# Logic_Probe_Ver_1.net
KiCad netlist of a schematic drawn in EAGLE
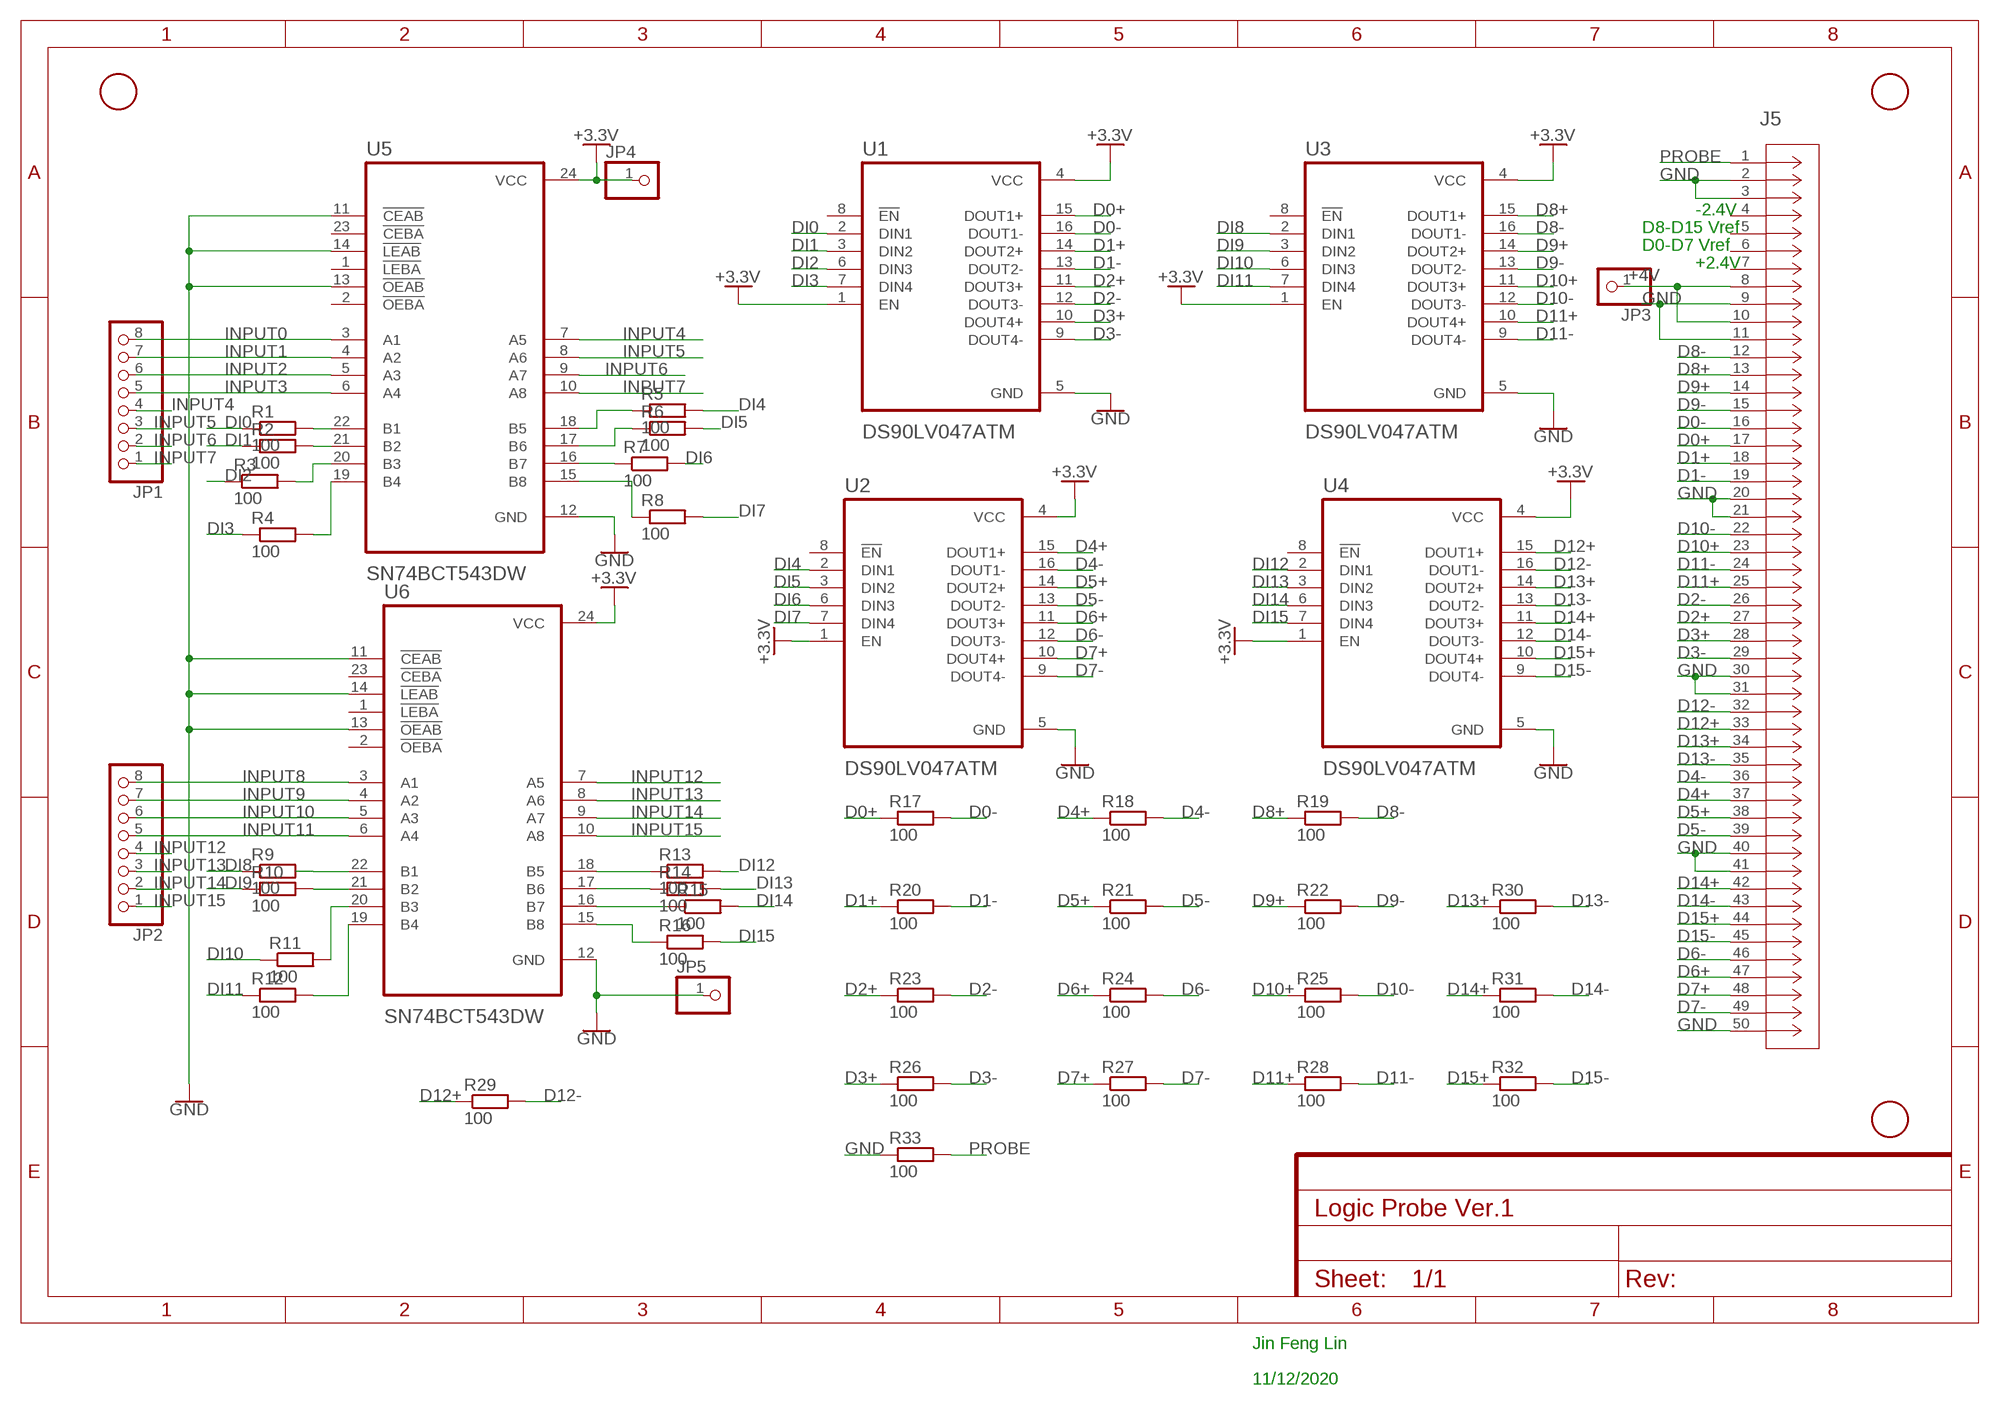
[diagram p0: schematic, sheet 1]

(export (version "E")
  (design (tool "Eeschema 10.0.6"))
  (components
    (comp (ref "J5")
      (value "TST-125-01-G-D")
      (footprint "eagle-import:CONN_TST-125-XX-X-D_SAI")
      (fields (field (name "COPYRIGHT") "Copyright (C) 2018 Accelerated Designs. All rights reserved"))
      (libsource (lib "eagle-import") (part "TST-125-01-G-D"))
    )
    (comp (ref "JP1")
      (value "PINHD-1X8LOCK")
      (footprint "eagle-import:1X08-LOCK")
      (libsource (lib "eagle-import") (part "PINHD-1X8LOCK"))
    )
    (comp (ref "JP2")
      (value "PINHD-1X8LOCK")
      (footprint "eagle-import:1X08-LOCK")
      (libsource (lib "eagle-import") (part "PINHD-1X8LOCK"))
    )
    (comp (ref "JP3")
      (value "PINHD-1X1")
      (footprint "eagle-import:1X01")
      (libsource (lib "eagle-import") (part "PINHD-1X1"))
    )
    (comp (ref "JP4")
      (value "PINHD-1X1")
      (footprint "eagle-import:1X01")
      (libsource (lib "eagle-import") (part "PINHD-1X1"))
    )
    (comp (ref "JP5")
      (value "PINHD-1X1")
      (footprint "eagle-import:1X01")
      (libsource (lib "eagle-import") (part "PINHD-1X1"))
    )
    (comp (ref "R1")
      (value "100")
      (footprint "eagle-import:R0805")
      (libsource (lib "eagle-import") (part "R-EU_R0805"))
    )
    (comp (ref "R2")
      (value "100")
      (footprint "eagle-import:R0805")
      (libsource (lib "eagle-import") (part "R-EU_R0805"))
    )
    (comp (ref "R3")
      (value "100")
      (footprint "eagle-import:R0805")
      (libsource (lib "eagle-import") (part "R-EU_R0805"))
    )
    (comp (ref "R4")
      (value "100")
      (footprint "eagle-import:R0805")
      (libsource (lib "eagle-import") (part "R-EU_R0805"))
    )
    (comp (ref "R5")
      (value "100")
      (footprint "eagle-import:R0805")
      (libsource (lib "eagle-import") (part "R-EU_R0805"))
    )
    (comp (ref "R6")
      (value "100")
      (footprint "eagle-import:R0805")
      (libsource (lib "eagle-import") (part "R-EU_R0805"))
    )
    (comp (ref "R7")
      (value "100")
      (footprint "eagle-import:R0805")
      (libsource (lib "eagle-import") (part "R-EU_R0805"))
    )
    (comp (ref "R8")
      (value "100")
      (footprint "eagle-import:R0805")
      (libsource (lib "eagle-import") (part "R-EU_R0805"))
    )
    (comp (ref "R9")
      (value "100")
      (footprint "eagle-import:R0805")
      (libsource (lib "eagle-import") (part "R-EU_R0805"))
    )
    (comp (ref "R10")
      (value "100")
      (footprint "eagle-import:R0805")
      (libsource (lib "eagle-import") (part "R-EU_R0805"))
    )
    (comp (ref "R11")
      (value "100")
      (footprint "eagle-import:R0805")
      (libsource (lib "eagle-import") (part "R-EU_R0805"))
    )
    (comp (ref "R12")
      (value "100")
      (footprint "eagle-import:R0805")
      (libsource (lib "eagle-import") (part "R-EU_R0805"))
    )
    (comp (ref "R13")
      (value "100")
      (footprint "eagle-import:R0805")
      (libsource (lib "eagle-import") (part "R-EU_R0805"))
    )
    (comp (ref "R14")
      (value "100")
      (footprint "eagle-import:R0805")
      (libsource (lib "eagle-import") (part "R-EU_R0805"))
    )
    (comp (ref "R15")
      (value "100")
      (footprint "eagle-import:R0805")
      (libsource (lib "eagle-import") (part "R-EU_R0805"))
    )
    (comp (ref "R16")
      (value "100")
      (footprint "eagle-import:R0805")
      (libsource (lib "eagle-import") (part "R-EU_R0805"))
    )
    (comp (ref "R17")
      (value "100")
      (footprint "eagle-import:R0805")
      (libsource (lib "eagle-import") (part "R-EU_R0805"))
    )
    (comp (ref "R18")
      (value "100")
      (footprint "eagle-import:R0805")
      (libsource (lib "eagle-import") (part "R-EU_R0805"))
    )
    (comp (ref "R19")
      (value "100")
      (footprint "eagle-import:R0805")
      (libsource (lib "eagle-import") (part "R-EU_R0805"))
    )
    (comp (ref "R20")
      (value "100")
      (footprint "eagle-import:R0805")
      (libsource (lib "eagle-import") (part "R-EU_R0805"))
    )
    (comp (ref "R21")
      (value "100")
      (footprint "eagle-import:R0805")
      (libsource (lib "eagle-import") (part "R-EU_R0805"))
    )
    (comp (ref "R22")
      (value "100")
      (footprint "eagle-import:R0805")
      (libsource (lib "eagle-import") (part "R-EU_R0805"))
    )
    (comp (ref "R23")
      (value "100")
      (footprint "eagle-import:R0805")
      (libsource (lib "eagle-import") (part "R-EU_R0805"))
    )
    (comp (ref "R24")
      (value "100")
      (footprint "eagle-import:R0805")
      (libsource (lib "eagle-import") (part "R-EU_R0805"))
    )
    (comp (ref "R25")
      (value "100")
      (footprint "eagle-import:R0805")
      (libsource (lib "eagle-import") (part "R-EU_R0805"))
    )
    (comp (ref "R26")
      (value "100")
      (footprint "eagle-import:R0805")
      (libsource (lib "eagle-import") (part "R-EU_R0805"))
    )
    (comp (ref "R27")
      (value "100")
      (footprint "eagle-import:R0805")
      (libsource (lib "eagle-import") (part "R-EU_R0805"))
    )
    (comp (ref "R28")
      (value "100")
      (footprint "eagle-import:R0805")
      (libsource (lib "eagle-import") (part "R-EU_R0805"))
    )
    (comp (ref "R29")
      (value "100")
      (footprint "eagle-import:R0805")
      (libsource (lib "eagle-import") (part "R-EU_R0805"))
    )
    (comp (ref "R30")
      (value "100")
      (footprint "eagle-import:R0805")
      (libsource (lib "eagle-import") (part "R-EU_R0805"))
    )
    (comp (ref "R31")
      (value "100")
      (footprint "eagle-import:R0805")
      (libsource (lib "eagle-import") (part "R-EU_R0805"))
    )
    (comp (ref "R32")
      (value "100")
      (footprint "eagle-import:R0805")
      (libsource (lib "eagle-import") (part "R-EU_R0805"))
    )
    (comp (ref "R33")
      (value "100")
      (footprint "eagle-import:R0805")
      (libsource (lib "eagle-import") (part "R-EU_R0805"))
    )
    (comp (ref "U$1")
      (value "FIDUCIAL")
      (footprint "eagle-import:FIDUCIAL_1MM")
      (libsource (lib "eagle-import") (part "FIDUCIAL"))
    )
    (comp (ref "U$2")
      (value "FIDUCIAL")
      (footprint "eagle-import:FIDUCIAL_1MM")
      (libsource (lib "eagle-import") (part "FIDUCIAL"))
    )
    (comp (ref "U$3")
      (value "FIDUCIAL")
      (footprint "eagle-import:FIDUCIAL_1MM")
      (libsource (lib "eagle-import") (part "FIDUCIAL"))
    )
    (comp (ref "U1")
      (value "DS90LV047ATM")
      (footprint "eagle-import:SOIC127P600X175-16N")
      (libsource (lib "eagle-import") (part "DS90LV047ATM"))
    )
    (comp (ref "U2")
      (value "DS90LV047ATM")
      (footprint "eagle-import:SOIC127P600X175-16N")
      (libsource (lib "eagle-import") (part "DS90LV047ATM"))
    )
    (comp (ref "U3")
      (value "DS90LV047ATM")
      (footprint "eagle-import:SOIC127P600X175-16N")
      (libsource (lib "eagle-import") (part "DS90LV047ATM"))
    )
    (comp (ref "U4")
      (value "DS90LV047ATM")
      (footprint "eagle-import:SOIC127P600X175-16N")
      (libsource (lib "eagle-import") (part "DS90LV047ATM"))
    )
    (comp (ref "U5")
      (value "SN74BCT543DW")
      (footprint "eagle-import:SOIC127P1030X265-24N")
      (fields (field (name "MF") "Texas Instruments"))
      (libsource (lib "eagle-import") (part "SN74BCT543DW"))
    )
    (comp (ref "U6")
      (value "SN74BCT543DW")
      (footprint "eagle-import:SOIC127P1030X265-24N")
      (fields (field (name "MF") "Texas Instruments"))
      (libsource (lib "eagle-import") (part "SN74BCT543DW"))
    )
  )
  (nets
    (net (code "1") (name "+3.3V") (class "Default")
      (node (ref "JP4") (pin "1") (pinfunction "1_1") (pintype "passive"))
      (node (ref "U1") (pin "1") (pinfunction "EN_1") (pintype "input"))
      (node (ref "U1") (pin "4") (pinfunction "VCC_4") (pintype "power_in"))
      (node (ref "U2") (pin "1") (pinfunction "EN_1") (pintype "input"))
      (node (ref "U2") (pin "4") (pinfunction "VCC_4") (pintype "power_in"))
      (node (ref "U3") (pin "1") (pinfunction "EN_1") (pintype "input"))
      (node (ref "U3") (pin "4") (pinfunction "VCC_4") (pintype "power_in"))
      (node (ref "U4") (pin "1") (pinfunction "EN_1") (pintype "input"))
      (node (ref "U4") (pin "4") (pinfunction "VCC_4") (pintype "power_in"))
      (node (ref "U5") (pin "24") (pinfunction "VCC_24") (pintype "power_in"))
      (node (ref "U6") (pin "24") (pinfunction "VCC_24") (pintype "power_in"))
    )
    (net (code "2") (name "/+4V") (class "Default")
      (node (ref "J5") (pin "10") (pinfunction "10_10") (pintype "passive"))
      (node (ref "J5") (pin "8") (pinfunction "8_8") (pintype "passive"))
      (node (ref "JP3") (pin "1") (pinfunction "1_1") (pintype "passive"))
    )
    (net (code "3") (name "/D0+") (class "Default")
      (node (ref "J5") (pin "17") (pinfunction "17_17") (pintype "passive"))
      (node (ref "R17") (pin "1") (pinfunction "1_1") (pintype "passive"))
      (node (ref "U1") (pin "15") (pinfunction "DOUT1+_15") (pintype "output"))
    )
    (net (code "4") (name "/D0-") (class "Default")
      (node (ref "J5") (pin "16") (pinfunction "16_16") (pintype "passive"))
      (node (ref "R17") (pin "2") (pinfunction "2_2") (pintype "passive"))
      (node (ref "U1") (pin "16") (pinfunction "DOUT1-_16") (pintype "output"))
    )
    (net (code "5") (name "/D1+") (class "Default")
      (node (ref "J5") (pin "18") (pinfunction "18_18") (pintype "passive"))
      (node (ref "R20") (pin "1") (pinfunction "1_1") (pintype "passive"))
      (node (ref "U1") (pin "14") (pinfunction "DOUT2+_14") (pintype "output"))
    )
    (net (code "6") (name "/D1-") (class "Default")
      (node (ref "J5") (pin "19") (pinfunction "19_19") (pintype "passive"))
      (node (ref "R20") (pin "2") (pinfunction "2_2") (pintype "passive"))
      (node (ref "U1") (pin "13") (pinfunction "DOUT2-_13") (pintype "output"))
    )
    (net (code "7") (name "/D2+") (class "Default")
      (node (ref "J5") (pin "27") (pinfunction "27_27") (pintype "passive"))
      (node (ref "R23") (pin "1") (pinfunction "1_1") (pintype "passive"))
      (node (ref "U1") (pin "11") (pinfunction "DOUT3+_11") (pintype "output"))
    )
    (net (code "8") (name "/D2-") (class "Default")
      (node (ref "J5") (pin "26") (pinfunction "26_26") (pintype "passive"))
      (node (ref "R23") (pin "2") (pinfunction "2_2") (pintype "passive"))
      (node (ref "U1") (pin "12") (pinfunction "DOUT3-_12") (pintype "output"))
    )
    (net (code "9") (name "/D3+") (class "Default")
      (node (ref "J5") (pin "28") (pinfunction "28_28") (pintype "passive"))
      (node (ref "R26") (pin "1") (pinfunction "1_1") (pintype "passive"))
      (node (ref "U1") (pin "10") (pinfunction "DOUT4+_10") (pintype "output"))
    )
    (net (code "10") (name "/D3-") (class "Default")
      (node (ref "J5") (pin "29") (pinfunction "29_29") (pintype "passive"))
      (node (ref "R26") (pin "2") (pinfunction "2_2") (pintype "passive"))
      (node (ref "U1") (pin "9") (pinfunction "DOUT4-_9") (pintype "output"))
    )
    (net (code "11") (name "/D4+") (class "Default")
      (node (ref "J5") (pin "37") (pinfunction "37_37") (pintype "passive"))
      (node (ref "R18") (pin "1") (pinfunction "1_1") (pintype "passive"))
      (node (ref "U2") (pin "15") (pinfunction "DOUT1+_15") (pintype "output"))
    )
    (net (code "12") (name "/D4-") (class "Default")
      (node (ref "J5") (pin "36") (pinfunction "36_36") (pintype "passive"))
      (node (ref "R18") (pin "2") (pinfunction "2_2") (pintype "passive"))
      (node (ref "U2") (pin "16") (pinfunction "DOUT1-_16") (pintype "output"))
    )
    (net (code "13") (name "/D5+") (class "Default")
      (node (ref "J5") (pin "38") (pinfunction "38_38") (pintype "passive"))
      (node (ref "R21") (pin "1") (pinfunction "1_1") (pintype "passive"))
      (node (ref "U2") (pin "14") (pinfunction "DOUT2+_14") (pintype "output"))
    )
    (net (code "14") (name "/D5-") (class "Default")
      (node (ref "J5") (pin "39") (pinfunction "39_39") (pintype "passive"))
      (node (ref "R21") (pin "2") (pinfunction "2_2") (pintype "passive"))
      (node (ref "U2") (pin "13") (pinfunction "DOUT2-_13") (pintype "output"))
    )
    (net (code "15") (name "/D6+") (class "Default")
      (node (ref "J5") (pin "47") (pinfunction "47_47") (pintype "passive"))
      (node (ref "R24") (pin "1") (pinfunction "1_1") (pintype "passive"))
      (node (ref "U2") (pin "11") (pinfunction "DOUT3+_11") (pintype "output"))
    )
    (net (code "16") (name "/D6-") (class "Default")
      (node (ref "J5") (pin "46") (pinfunction "46_46") (pintype "passive"))
      (node (ref "R24") (pin "2") (pinfunction "2_2") (pintype "passive"))
      (node (ref "U2") (pin "12") (pinfunction "DOUT3-_12") (pintype "output"))
    )
    (net (code "17") (name "/D7+") (class "Default")
      (node (ref "J5") (pin "48") (pinfunction "48_48") (pintype "passive"))
      (node (ref "R27") (pin "1") (pinfunction "1_1") (pintype "passive"))
      (node (ref "U2") (pin "10") (pinfunction "DOUT4+_10") (pintype "output"))
    )
    (net (code "18") (name "/D7-") (class "Default")
      (node (ref "J5") (pin "49") (pinfunction "49_49") (pintype "passive"))
      (node (ref "R27") (pin "2") (pinfunction "2_2") (pintype "passive"))
      (node (ref "U2") (pin "9") (pinfunction "DOUT4-_9") (pintype "output"))
    )
    (net (code "19") (name "/D8+") (class "Default")
      (node (ref "J5") (pin "13") (pinfunction "13_13") (pintype "passive"))
      (node (ref "R19") (pin "1") (pinfunction "1_1") (pintype "passive"))
      (node (ref "U3") (pin "15") (pinfunction "DOUT1+_15") (pintype "output"))
    )
    (net (code "20") (name "/D8-") (class "Default")
      (node (ref "J5") (pin "12") (pinfunction "12_12") (pintype "passive"))
      (node (ref "R19") (pin "2") (pinfunction "2_2") (pintype "passive"))
      (node (ref "U3") (pin "16") (pinfunction "DOUT1-_16") (pintype "output"))
    )
    (net (code "21") (name "/D9+") (class "Default")
      (node (ref "J5") (pin "14") (pinfunction "14_14") (pintype "passive"))
      (node (ref "R22") (pin "1") (pinfunction "1_1") (pintype "passive"))
      (node (ref "U3") (pin "14") (pinfunction "DOUT2+_14") (pintype "output"))
    )
    (net (code "22") (name "/D9-") (class "Default")
      (node (ref "J5") (pin "15") (pinfunction "15_15") (pintype "passive"))
      (node (ref "R22") (pin "2") (pinfunction "2_2") (pintype "passive"))
      (node (ref "U3") (pin "13") (pinfunction "DOUT2-_13") (pintype "output"))
    )
    (net (code "23") (name "/D10+") (class "Default")
      (node (ref "J5") (pin "23") (pinfunction "23_23") (pintype "passive"))
      (node (ref "R25") (pin "1") (pinfunction "1_1") (pintype "passive"))
      (node (ref "U3") (pin "11") (pinfunction "DOUT3+_11") (pintype "output"))
    )
    (net (code "24") (name "/D10-") (class "Default")
      (node (ref "J5") (pin "22") (pinfunction "22_22") (pintype "passive"))
      (node (ref "R25") (pin "2") (pinfunction "2_2") (pintype "passive"))
      (node (ref "U3") (pin "12") (pinfunction "DOUT3-_12") (pintype "output"))
    )
    (net (code "25") (name "/D11+") (class "Default")
      (node (ref "J5") (pin "25") (pinfunction "25_25") (pintype "passive"))
      (node (ref "R28") (pin "1") (pinfunction "1_1") (pintype "passive"))
      (node (ref "U3") (pin "10") (pinfunction "DOUT4+_10") (pintype "output"))
    )
    (net (code "26") (name "/D11-") (class "Default")
      (node (ref "J5") (pin "24") (pinfunction "24_24") (pintype "passive"))
      (node (ref "R28") (pin "2") (pinfunction "2_2") (pintype "passive"))
      (node (ref "U3") (pin "9") (pinfunction "DOUT4-_9") (pintype "output"))
    )
    (net (code "27") (name "/D12+") (class "Default")
      (node (ref "J5") (pin "33") (pinfunction "33_33") (pintype "passive"))
      (node (ref "R29") (pin "1") (pinfunction "1_1") (pintype "passive"))
      (node (ref "U4") (pin "15") (pinfunction "DOUT1+_15") (pintype "output"))
    )
    (net (code "28") (name "/D12-") (class "Default")
      (node (ref "J5") (pin "32") (pinfunction "32_32") (pintype "passive"))
      (node (ref "R29") (pin "2") (pinfunction "2_2") (pintype "passive"))
      (node (ref "U4") (pin "16") (pinfunction "DOUT1-_16") (pintype "output"))
    )
    (net (code "29") (name "/D13+") (class "Default")
      (node (ref "J5") (pin "34") (pinfunction "34_34") (pintype "passive"))
      (node (ref "R30") (pin "1") (pinfunction "1_1") (pintype "passive"))
      (node (ref "U4") (pin "14") (pinfunction "DOUT2+_14") (pintype "output"))
    )
    (net (code "30") (name "/D13-") (class "Default")
      (node (ref "J5") (pin "35") (pinfunction "35_35") (pintype "passive"))
      (node (ref "R30") (pin "2") (pinfunction "2_2") (pintype "passive"))
      (node (ref "U4") (pin "13") (pinfunction "DOUT2-_13") (pintype "output"))
    )
    (net (code "31") (name "/D14+") (class "Default")
      (node (ref "J5") (pin "42") (pinfunction "42_42") (pintype "passive"))
      (node (ref "R31") (pin "1") (pinfunction "1_1") (pintype "passive"))
      (node (ref "U4") (pin "11") (pinfunction "DOUT3+_11") (pintype "output"))
    )
    (net (code "32") (name "/D14-") (class "Default")
      (node (ref "J5") (pin "43") (pinfunction "43_43") (pintype "passive"))
      (node (ref "R31") (pin "2") (pinfunction "2_2") (pintype "passive"))
      (node (ref "U4") (pin "12") (pinfunction "DOUT3-_12") (pintype "output"))
    )
    (net (code "33") (name "/D15+") (class "Default")
      (node (ref "J5") (pin "44") (pinfunction "44_44") (pintype "passive"))
      (node (ref "R32") (pin "1") (pinfunction "1_1") (pintype "passive"))
      (node (ref "U4") (pin "10") (pinfunction "DOUT4+_10") (pintype "output"))
    )
    (net (code "34") (name "/D15-") (class "Default")
      (node (ref "J5") (pin "45") (pinfunction "45_45") (pintype "passive"))
      (node (ref "R32") (pin "2") (pinfunction "2_2") (pintype "passive"))
      (node (ref "U4") (pin "9") (pinfunction "DOUT4-_9") (pintype "output"))
    )
    (net (code "35") (name "/DI0") (class "Default")
      (node (ref "R1") (pin "1") (pinfunction "1_1") (pintype "passive"))
      (node (ref "U1") (pin "2") (pinfunction "DIN1_2") (pintype "input"))
    )
    (net (code "36") (name "/DI1") (class "Default")
      (node (ref "R2") (pin "1") (pinfunction "1_1") (pintype "passive"))
      (node (ref "U1") (pin "3") (pinfunction "DIN2_3") (pintype "input"))
    )
    (net (code "37") (name "/DI2") (class "Default")
      (node (ref "R3") (pin "1") (pinfunction "1_1") (pintype "passive"))
      (node (ref "U1") (pin "6") (pinfunction "DIN3_6") (pintype "input"))
    )
    (net (code "38") (name "/DI3") (class "Default")
      (node (ref "R4") (pin "1") (pinfunction "1_1") (pintype "passive"))
      (node (ref "U1") (pin "7") (pinfunction "DIN4_7") (pintype "input"))
    )
    (net (code "39") (name "/DI4") (class "Default")
      (node (ref "R5") (pin "2") (pinfunction "2_2") (pintype "passive"))
      (node (ref "U2") (pin "2") (pinfunction "DIN1_2") (pintype "input"))
    )
    (net (code "40") (name "/DI5") (class "Default")
      (node (ref "R6") (pin "2") (pinfunction "2_2") (pintype "passive"))
      (node (ref "U2") (pin "3") (pinfunction "DIN2_3") (pintype "input"))
    )
    (net (code "41") (name "/DI6") (class "Default")
      (node (ref "R7") (pin "2") (pinfunction "2_2") (pintype "passive"))
      (node (ref "U2") (pin "6") (pinfunction "DIN3_6") (pintype "input"))
    )
    (net (code "42") (name "/DI7") (class "Default")
      (node (ref "R8") (pin "2") (pinfunction "2_2") (pintype "passive"))
      (node (ref "U2") (pin "7") (pinfunction "DIN4_7") (pintype "input"))
    )
    (net (code "43") (name "/DI8") (class "Default")
      (node (ref "R9") (pin "1") (pinfunction "1_1") (pintype "passive"))
      (node (ref "U3") (pin "2") (pinfunction "DIN1_2") (pintype "input"))
    )
    (net (code "44") (name "/DI9") (class "Default")
      (node (ref "R10") (pin "1") (pinfunction "1_1") (pintype "passive"))
      (node (ref "U3") (pin "3") (pinfunction "DIN2_3") (pintype "input"))
    )
    (net (code "45") (name "/DI10") (class "Default")
      (node (ref "R11") (pin "1") (pinfunction "1_1") (pintype "passive"))
      (node (ref "U3") (pin "6") (pinfunction "DIN3_6") (pintype "input"))
    )
    (net (code "46") (name "/DI11") (class "Default")
      (node (ref "R12") (pin "1") (pinfunction "1_1") (pintype "passive"))
      (node (ref "U3") (pin "7") (pinfunction "DIN4_7") (pintype "input"))
    )
    (net (code "47") (name "/DI12") (class "Default")
      (node (ref "R13") (pin "2") (pinfunction "2_2") (pintype "passive"))
      (node (ref "U4") (pin "2") (pinfunction "DIN1_2") (pintype "input"))
    )
    (net (code "48") (name "/DI13") (class "Default")
      (node (ref "R14") (pin "2") (pinfunction "2_2") (pintype "passive"))
      (node (ref "U4") (pin "3") (pinfunction "DIN2_3") (pintype "input"))
    )
    (net (code "49") (name "/DI14") (class "Default")
      (node (ref "R15") (pin "2") (pinfunction "2_2") (pintype "passive"))
      (node (ref "U4") (pin "6") (pinfunction "DIN3_6") (pintype "input"))
    )
    (net (code "50") (name "/DI15") (class "Default")
      (node (ref "R16") (pin "2") (pinfunction "2_2") (pintype "passive"))
      (node (ref "U4") (pin "7") (pinfunction "DIN4_7") (pintype "input"))
    )
    (net (code "51") (name "/INPUT0") (class "Default")
      (node (ref "JP1") (pin "8") (pinfunction "8_8") (pintype "passive"))
      (node (ref "U5") (pin "3") (pinfunction "A1_3") (pintype "bidirectional"))
    )
    (net (code "52") (name "/INPUT1") (class "Default")
      (node (ref "JP1") (pin "7") (pinfunction "7_7") (pintype "passive"))
      (node (ref "U5") (pin "4") (pinfunction "A2_4") (pintype "bidirectional"))
    )
    (net (code "53") (name "/INPUT2") (class "Default")
      (node (ref "JP1") (pin "6") (pinfunction "6_6") (pintype "passive"))
      (node (ref "U5") (pin "5") (pinfunction "A3_5") (pintype "bidirectional"))
    )
    (net (code "54") (name "/INPUT3") (class "Default")
      (node (ref "JP1") (pin "5") (pinfunction "5_5") (pintype "passive"))
      (node (ref "U5") (pin "6") (pinfunction "A4_6") (pintype "bidirectional"))
    )
    (net (code "55") (name "/INPUT4") (class "Default")
      (node (ref "JP1") (pin "4") (pinfunction "4_4") (pintype "passive"))
      (node (ref "U5") (pin "7") (pinfunction "A5_7") (pintype "bidirectional"))
    )
    (net (code "56") (name "/INPUT5") (class "Default")
      (node (ref "JP1") (pin "3") (pinfunction "3_3") (pintype "passive"))
      (node (ref "U5") (pin "8") (pinfunction "A6_8") (pintype "bidirectional"))
    )
    (net (code "57") (name "/INPUT6") (class "Default")
      (node (ref "JP1") (pin "2") (pinfunction "2_2") (pintype "passive"))
      (node (ref "U5") (pin "9") (pinfunction "A7_9") (pintype "bidirectional"))
    )
    (net (code "58") (name "/INPUT7") (class "Default")
      (node (ref "JP1") (pin "1") (pinfunction "1_1") (pintype "passive"))
      (node (ref "U5") (pin "10") (pinfunction "A8_10") (pintype "bidirectional"))
    )
    (net (code "59") (name "/INPUT8") (class "Default")
      (node (ref "JP2") (pin "8") (pinfunction "8_8") (pintype "passive"))
      (node (ref "U6") (pin "3") (pinfunction "A1_3") (pintype "bidirectional"))
    )
    (net (code "60") (name "/INPUT9") (class "Default")
      (node (ref "JP2") (pin "7") (pinfunction "7_7") (pintype "passive"))
      (node (ref "U6") (pin "4") (pinfunction "A2_4") (pintype "bidirectional"))
    )
    (net (code "61") (name "/INPUT10") (class "Default")
      (node (ref "JP2") (pin "6") (pinfunction "6_6") (pintype "passive"))
      (node (ref "U6") (pin "5") (pinfunction "A3_5") (pintype "bidirectional"))
    )
    (net (code "62") (name "/INPUT11") (class "Default")
      (node (ref "JP2") (pin "5") (pinfunction "5_5") (pintype "passive"))
      (node (ref "U6") (pin "6") (pinfunction "A4_6") (pintype "bidirectional"))
    )
    (net (code "63") (name "/INPUT12") (class "Default")
      (node (ref "JP2") (pin "4") (pinfunction "4_4") (pintype "passive"))
      (node (ref "U6") (pin "7") (pinfunction "A5_7") (pintype "bidirectional"))
    )
    (net (code "64") (name "/INPUT13") (class "Default")
      (node (ref "JP2") (pin "3") (pinfunction "3_3") (pintype "passive"))
      (node (ref "U6") (pin "8") (pinfunction "A6_8") (pintype "bidirectional"))
    )
    (net (code "65") (name "/INPUT14") (class "Default")
      (node (ref "JP2") (pin "2") (pinfunction "2_2") (pintype "passive"))
      (node (ref "U6") (pin "9") (pinfunction "A7_9") (pintype "bidirectional"))
    )
    (net (code "66") (name "/INPUT15") (class "Default")
      (node (ref "JP2") (pin "1") (pinfunction "1_1") (pintype "passive"))
      (node (ref "U6") (pin "10") (pinfunction "A8_10") (pintype "bidirectional"))
    )
    (net (code "67") (name "/PROBE") (class "Default")
      (node (ref "J5") (pin "1") (pinfunction "1_1") (pintype "passive"))
      (node (ref "R33") (pin "2") (pinfunction "2_2") (pintype "passive"))
    )
    (net (code "68") (name "GND") (class "Default")
      (node (ref "J5") (pin "11") (pinfunction "11_11") (pintype "passive"))
      (node (ref "J5") (pin "2") (pinfunction "2_2") (pintype "passive"))
      (node (ref "J5") (pin "20") (pinfunction "20_20") (pintype "passive"))
      (node (ref "J5") (pin "21") (pinfunction "21_21") (pintype "passive"))
      (node (ref "J5") (pin "3") (pinfunction "3_3") (pintype "passive"))
      (node (ref "J5") (pin "30") (pinfunction "30_30") (pintype "passive"))
      (node (ref "J5") (pin "31") (pinfunction "31_31") (pintype "passive"))
      (node (ref "J5") (pin "40") (pinfunction "40_40") (pintype "passive"))
      (node (ref "J5") (pin "41") (pinfunction "41_41") (pintype "passive"))
      (node (ref "J5") (pin "50") (pinfunction "50_50") (pintype "passive"))
      (node (ref "J5") (pin "9") (pinfunction "9_9") (pintype "passive"))
      (node (ref "JP5") (pin "1") (pinfunction "1_1") (pintype "passive"))
      (node (ref "R33") (pin "1") (pinfunction "1_1") (pintype "passive"))
      (node (ref "U1") (pin "5") (pinfunction "GND_5") (pintype "power_in"))
      (node (ref "U2") (pin "5") (pinfunction "GND_5") (pintype "power_in"))
      (node (ref "U3") (pin "5") (pinfunction "GND_5") (pintype "power_in"))
      (node (ref "U4") (pin "5") (pinfunction "GND_5") (pintype "power_in"))
      (node (ref "U5") (pin "11") (pinfunction "~{CEAB}_11") (pintype "input"))
      (node (ref "U5") (pin "12") (pinfunction "GND_12") (pintype "power_in"))
      (node (ref "U5") (pin "13") (pinfunction "~{OEAB}_13") (pintype "input"))
      (node (ref "U5") (pin "14") (pinfunction "~{LEAB}_14") (pintype "input"))
      (node (ref "U6") (pin "11") (pinfunction "~{CEAB}_11") (pintype "input"))
      (node (ref "U6") (pin "12") (pinfunction "GND_12") (pintype "power_in"))
      (node (ref "U6") (pin "13") (pinfunction "~{OEAB}_13") (pintype "input"))
      (node (ref "U6") (pin "14") (pinfunction "~{LEAB}_14") (pintype "input"))
    )
    (net (code "69") (name "Net-(U5-B1)") (class "Default")
      (node (ref "R1") (pin "2") (pinfunction "2_2") (pintype "passive"))
      (node (ref "U5") (pin "22") (pinfunction "B1_22") (pintype "bidirectional"))
    )
    (net (code "70") (name "Net-(U5-B2)") (class "Default")
      (node (ref "R2") (pin "2") (pinfunction "2_2") (pintype "passive"))
      (node (ref "U5") (pin "21") (pinfunction "B2_21") (pintype "bidirectional"))
    )
    (net (code "71") (name "Net-(U5-B3)") (class "Default")
      (node (ref "R3") (pin "2") (pinfunction "2_2") (pintype "passive"))
      (node (ref "U5") (pin "20") (pinfunction "B3_20") (pintype "bidirectional"))
    )
    (net (code "72") (name "Net-(U5-B4)") (class "Default")
      (node (ref "R4") (pin "2") (pinfunction "2_2") (pintype "passive"))
      (node (ref "U5") (pin "19") (pinfunction "B4_19") (pintype "bidirectional"))
    )
    (net (code "73") (name "Net-(U5-B5)") (class "Default")
      (node (ref "R5") (pin "1") (pinfunction "1_1") (pintype "passive"))
      (node (ref "U5") (pin "18") (pinfunction "B5_18") (pintype "bidirectional"))
    )
    (net (code "74") (name "Net-(U5-B6)") (class "Default")
      (node (ref "R6") (pin "1") (pinfunction "1_1") (pintype "passive"))
      (node (ref "U5") (pin "17") (pinfunction "B6_17") (pintype "bidirectional"))
    )
    (net (code "75") (name "Net-(U5-B7)") (class "Default")
      (node (ref "R7") (pin "1") (pinfunction "1_1") (pintype "passive"))
      (node (ref "U5") (pin "16") (pinfunction "B7_16") (pintype "bidirectional"))
    )
    (net (code "76") (name "Net-(U5-B8)") (class "Default")
      (node (ref "R8") (pin "1") (pinfunction "1_1") (pintype "passive"))
      (node (ref "U5") (pin "15") (pinfunction "B8_15") (pintype "bidirectional"))
    )
    (net (code "77") (name "Net-(U6-B1)") (class "Default")
      (node (ref "R9") (pin "2") (pinfunction "2_2") (pintype "passive"))
      (node (ref "U6") (pin "22") (pinfunction "B1_22") (pintype "bidirectional"))
    )
    (net (code "78") (name "Net-(U6-B2)") (class "Default")
      (node (ref "R10") (pin "2") (pinfunction "2_2") (pintype "passive"))
      (node (ref "U6") (pin "21") (pinfunction "B2_21") (pintype "bidirectional"))
    )
    (net (code "79") (name "Net-(U6-B3)") (class "Default")
      (node (ref "R11") (pin "2") (pinfunction "2_2") (pintype "passive"))
      (node (ref "U6") (pin "20") (pinfunction "B3_20") (pintype "bidirectional"))
    )
    (net (code "80") (name "Net-(U6-B4)") (class "Default")
      (node (ref "R12") (pin "2") (pinfunction "2_2") (pintype "passive"))
      (node (ref "U6") (pin "19") (pinfunction "B4_19") (pintype "bidirectional"))
    )
    (net (code "81") (name "Net-(U6-B5)") (class "Default")
      (node (ref "R13") (pin "1") (pinfunction "1_1") (pintype "passive"))
      (node (ref "U6") (pin "18") (pinfunction "B5_18") (pintype "bidirectional"))
    )
    (net (code "82") (name "Net-(U6-B6)") (class "Default")
      (node (ref "R14") (pin "1") (pinfunction "1_1") (pintype "passive"))
      (node (ref "U6") (pin "17") (pinfunction "B6_17") (pintype "bidirectional"))
    )
    (net (code "83") (name "Net-(U6-B7)") (class "Default")
      (node (ref "R15") (pin "1") (pinfunction "1_1") (pintype "passive"))
      (node (ref "U6") (pin "16") (pinfunction "B7_16") (pintype "bidirectional"))
    )
    (net (code "84") (name "Net-(U6-B8)") (class "Default")
      (node (ref "R16") (pin "1") (pinfunction "1_1") (pintype "passive"))
      (node (ref "U6") (pin "15") (pinfunction "B8_15") (pintype "bidirectional"))
    )
    (net (code "85") (name "unconnected-(J5-Pad4)") (class "Default")
      (node (ref "J5") (pin "4") (pinfunction "4_4") (pintype "passive"))
    )
    (net (code "86") (name "unconnected-(J5-Pad5)") (class "Default")
      (node (ref "J5") (pin "5") (pinfunction "5_5") (pintype "passive"))
    )
    (net (code "87") (name "unconnected-(J5-Pad6)") (class "Default")
      (node (ref "J5") (pin "6") (pinfunction "6_6") (pintype "passive"))
    )
    (net (code "88") (name "unconnected-(J5-Pad7)") (class "Default")
      (node (ref "J5") (pin "7") (pinfunction "7_7") (pintype "passive"))
    )
    (net (code "89") (name "unconnected-(U1-~{EN}-Pad8)") (class "Default")
      (node (ref "U1") (pin "8") (pinfunction "~{EN}_8") (pintype "input"))
    )
    (net (code "90") (name "unconnected-(U2-~{EN}-Pad8)") (class "Default")
      (node (ref "U2") (pin "8") (pinfunction "~{EN}_8") (pintype "input"))
    )
    (net (code "91") (name "unconnected-(U3-~{EN}-Pad8)") (class "Default")
      (node (ref "U3") (pin "8") (pinfunction "~{EN}_8") (pintype "input"))
    )
    (net (code "92") (name "unconnected-(U4-~{EN}-Pad8)") (class "Default")
      (node (ref "U4") (pin "8") (pinfunction "~{EN}_8") (pintype "input"))
    )
    (net (code "93") (name "unconnected-(U5-~{CEBA}-Pad23)") (class "Default")
      (node (ref "U5") (pin "23") (pinfunction "~{CEBA}_23") (pintype "input"))
    )
    (net (code "94") (name "unconnected-(U5-~{LEBA}-Pad1)") (class "Default")
      (node (ref "U5") (pin "1") (pinfunction "~{LEBA}_1") (pintype "input"))
    )
    (net (code "95") (name "unconnected-(U5-~{OEBA}-Pad2)") (class "Default")
      (node (ref "U5") (pin "2") (pinfunction "~{OEBA}_2") (pintype "input"))
    )
    (net (code "96") (name "unconnected-(U6-~{CEBA}-Pad23)") (class "Default")
      (node (ref "U6") (pin "23") (pinfunction "~{CEBA}_23") (pintype "input"))
    )
    (net (code "97") (name "unconnected-(U6-~{LEBA}-Pad1)") (class "Default")
      (node (ref "U6") (pin "1") (pinfunction "~{LEBA}_1") (pintype "input"))
    )
    (net (code "98") (name "unconnected-(U6-~{OEBA}-Pad2)") (class "Default")
      (node (ref "U6") (pin "2") (pinfunction "~{OEBA}_2") (pintype "input"))
    )
  )
)
